# external.net
KiCad netlist of a schematic drawn in Altium Designer
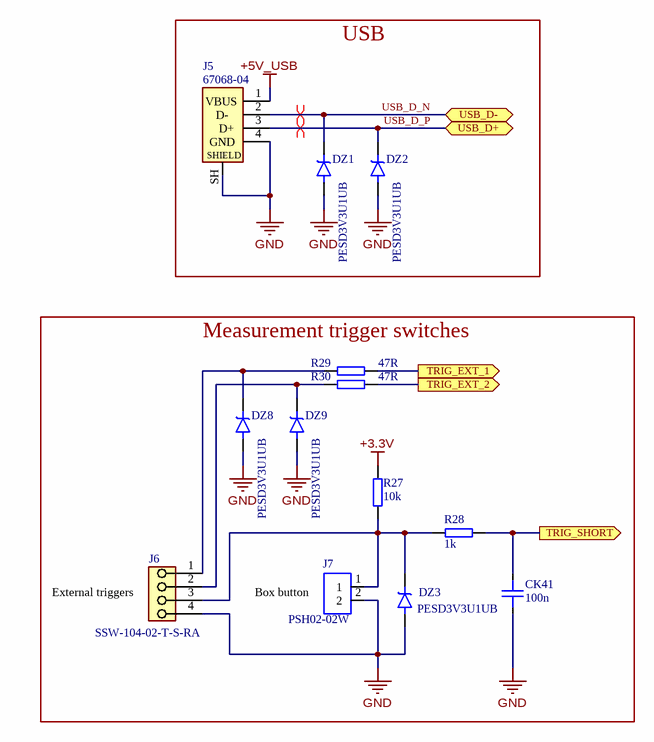
[diagram p0: external.SchDoc]

(export (version "E")
  (design (tool "Eeschema 10.0.6"))
  (components
    (comp (ref "CK41")
      (value "100n")
      (footprint "CAPC1608X09N(SMC0603)")
      (description "C; 100n; 50V; 10%; X7R; ??;")
      (fields
        (field (name "MANUFACTURER") "SAMSUNG EM: CL10B104KB8NNNC;;SAMSUNG EM: CL10B104KB8NNNO;;SAMSUNG EM: CL10B104KB8NNND")
      )
      (libsource (lib "altium_sql") (part "CK"))
    )
    (comp (ref "DZ1")
      (value "PESD3V3U1UB")
      (footprint "SODFL160X65-2N(SC79)")
      (description "CP; Voltage [V] - Unidirectional; 4.5; R:Yes; 1x;")
      (fields (field (name "MANUFACTURER") "Nexperia: PESD3V3U1UB,115;;NXP: PESD3V3U1UB,115"))
      (libsource (lib "altium_sql") (part "DTU"))
    )
    (comp (ref "DZ2")
      (value "PESD3V3U1UB")
      (footprint "SODFL160X65-2N(SC79)")
      (description "CP; Voltage [V] - Unidirectional; 4.5; R:Yes; 1x;")
      (fields (field (name "MANUFACTURER") "Nexperia: PESD3V3U1UB,115;;NXP: PESD3V3U1UB,115"))
      (libsource (lib "altium_sql") (part "DTU"))
    )
    (comp (ref "DZ3")
      (value "PESD3V3U1UB")
      (footprint "SODFL160X65-2N(SC79)")
      (description "CP; Voltage [V] - Unidirectional; 4.5; R:Yes; 1x;")
      (fields (field (name "MANUFACTURER") "Nexperia: PESD3V3U1UB,115;;NXP: PESD3V3U1UB,115"))
      (libsource (lib "altium_sql") (part "DTU"))
    )
    (comp (ref "DZ8")
      (value "PESD3V3U1UB")
      (footprint "SODFL160X65-2N(SC79)")
      (description "CP; Voltage [V] - Unidirectional; 4.5; R:Yes; 1x;")
      (fields (field (name "MANUFACTURER") "Nexperia: PESD3V3U1UB,115;;NXP: PESD3V3U1UB,115"))
      (libsource (lib "altium_sql") (part "DTU"))
    )
    (comp (ref "DZ9")
      (value "PESD3V3U1UB")
      (footprint "SODFL160X65-2N(SC79)")
      (description "CP; Voltage [V] - Unidirectional; 4.5; R:Yes; 1x;")
      (fields (field (name "MANUFACTURER") "Nexperia: PESD3V3U1UB,115;;NXP: PESD3V3U1UB,115"))
      (libsource (lib "altium_sql") (part "DTU"))
    )
    (comp (ref "J5")
      (value "67068-04")
      (footprint "USB-B")
      (description "Con; USB; 1x; PCB; Right angle; 250V; 1.5A; Female; Gold; ??;")
      (fields (field (name "MANUFACTURER") "HSUAN MAO: C8317-04BFHSB0R;;HSM: C8317-04BFHSB0R"))
      (libsource (lib "altium_sql") (part "EJ_USB1"))
    )
    (comp (ref "J6")
      (value "SSW-104-02-T-S-RA")
      (footprint "SSW-104-02-T-S-RA")
      (description "Female Header, Single row, 1 x 4, R/A, THT")
      (libsource (lib "custom-footprints") (part "SSW-104-02-T-S-RA"))
    )
    (comp (ref "J7")
      (value "PSH02-02W")
      (footprint "Official_PSH0202W")
      (description "Con; PFH/PSH; 2x; PCB; Right angle; 250V; 3A; Male; Tin; ??;")
      (fields (field (name "MANUFACTURER") "Neltron: 2217R-XX-WH2"))
      (libsource (lib "altium_sql") (part "EJ-PSH0202WXX0"))
    )
    (comp (ref "R27")
      (value "10k")
      (footprint "RESC2012X06N(SMR0805)")
      (description "R; 10k; 0.125W; 1%; 150V; Thick Film; ±100ppm/K; 1x;")
      (libsource (lib "altium_sql") (part "R"))
    )
    (comp (ref "R28")
      (value "1k")
      (footprint "RESC2012X06N(SMR0805)")
      (description "R; 1k; 0.125W; 1%; 150V; Thick Film; ±100ppm/K; 1x;")
      (libsource (lib "altium_sql") (part "R"))
    )
    (comp (ref "R29")
      (value "47R")
      (footprint "RESC2012X06N(SMR0805)")
      (description "R; 47R; 0.125W; 1%; 150V; Thick Film; ±100ppm/K; 1x;")
      (libsource (lib "altium_sql") (part "R"))
    )
    (comp (ref "R30")
      (value "47R")
      (footprint "RESC2012X06N(SMR0805)")
      (description "R; 47R; 0.125W; 1%; 150V; Thick Film; ±100ppm/K; 1x;")
      (libsource (lib "altium_sql") (part "R"))
    )
  )
  (nets
    (net (code "1") (name "+3.3V") (class "Default")
      (node (ref "R27") (pin "2") (pinfunction "2_2") (pintype "passive"))
    )
    (net (code "2") (name "+5V_USB") (class "Default")
      (node (ref "J5") (pin "1") (pinfunction "VBUS_1") (pintype "passive"))
    )
    (net (code "3") (name "/TRIG_EXT_1") (class "Default")
      (node (ref "R29") (pin "1") (pinfunction "1_1") (pintype "passive"))
    )
    (net (code "4") (name "/TRIG_EXT_2") (class "Default")
      (node (ref "R30") (pin "1") (pinfunction "1_1") (pintype "passive"))
    )
    (net (code "5") (name "/TRIG_SHORT") (class "Default")
      (node (ref "CK41") (pin "1") (pinfunction "1_1") (pintype "passive"))
      (node (ref "R28") (pin "1") (pinfunction "1_1") (pintype "passive"))
    )
    (net (code "6") (name "/USB_D_N") (class "Default")
      (node (ref "DZ1") (pin "1") (pinfunction "C_1") (pintype "passive"))
      (node (ref "J5") (pin "2") (pinfunction "D-_2") (pintype "passive"))
    )
    (net (code "7") (name "/USB_D_P") (class "Default")
      (node (ref "DZ2") (pin "1") (pinfunction "C_1") (pintype "passive"))
      (node (ref "J5") (pin "3") (pinfunction "D+_3") (pintype "passive"))
    )
    (net (code "8") (name "GND") (class "Default")
      (node (ref "CK41") (pin "2") (pinfunction "2_2") (pintype "passive"))
      (node (ref "DZ1") (pin "2") (pinfunction "A_2") (pintype "passive"))
      (node (ref "DZ2") (pin "2") (pinfunction "A_2") (pintype "passive"))
      (node (ref "DZ3") (pin "2") (pinfunction "A_2") (pintype "passive"))
      (node (ref "DZ8") (pin "2") (pinfunction "A_2") (pintype "passive"))
      (node (ref "DZ9") (pin "2") (pinfunction "A_2") (pintype "passive"))
      (node (ref "J5") (pin "4") (pinfunction "GND_4") (pintype "passive"))
      (node (ref "J5") (pin "SH") (pinfunction "SHIELD_SH") (pintype "passive"))
      (node (ref "J6") (pin "4") (pinfunction "4_4") (pintype "passive"))
      (node (ref "J7") (pin "2") (pinfunction "2_2") (pintype "passive"))
    )
    (net (code "9") (name "Net-(DZ3-C)") (class "Default")
      (node (ref "DZ3") (pin "1") (pinfunction "C_1") (pintype "passive"))
      (node (ref "J6") (pin "3") (pinfunction "3_3") (pintype "passive"))
      (node (ref "J7") (pin "1") (pinfunction "1_1") (pintype "passive"))
      (node (ref "R27") (pin "1") (pinfunction "1_1") (pintype "passive"))
      (node (ref "R28") (pin "2") (pinfunction "2_2") (pintype "passive"))
    )
    (net (code "10") (name "Net-(DZ8-C)") (class "Default")
      (node (ref "DZ8") (pin "1") (pinfunction "C_1") (pintype "passive"))
      (node (ref "J6") (pin "1") (pinfunction "1_1") (pintype "passive"))
      (node (ref "R29") (pin "2") (pinfunction "2_2") (pintype "passive"))
    )
    (net (code "11") (name "Net-(DZ9-C)") (class "Default")
      (node (ref "DZ9") (pin "1") (pinfunction "C_1") (pintype "passive"))
      (node (ref "J6") (pin "2") (pinfunction "2_2") (pintype "passive"))
      (node (ref "R30") (pin "2") (pinfunction "2_2") (pintype "passive"))
    )
  )
)
